# P12_SPI_NAND_FLASH.net
KiCad netlist of a schematic drawn in Altium Designer
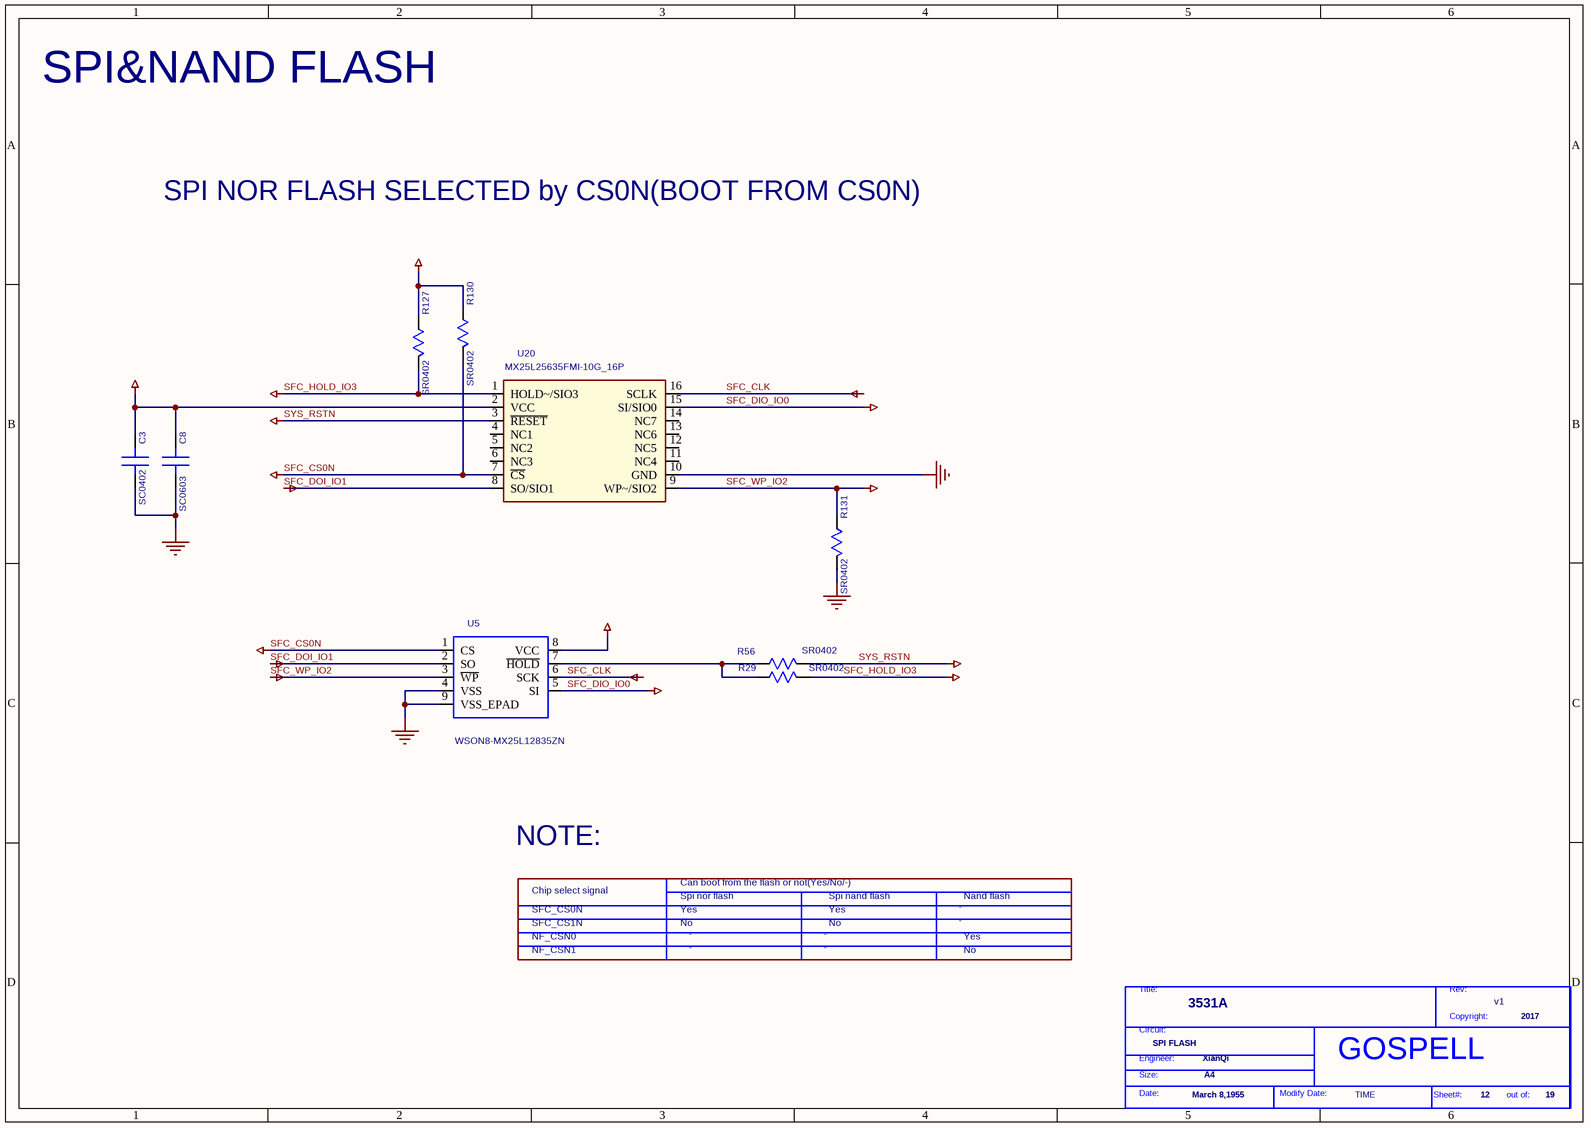
[diagram p0: P12 SPI&NAND FLASH.SchDoc]

(export (version "E")
  (design (tool "Eeschema 10.0.6"))
  (components
    (comp (ref "C3") (value "SC0402") (libsource (lib "*") (part "C_0_Dup2")))
    (comp (ref "C8") (value "SC0603") (libsource (lib "*") (part "C_0_Dup1")))
    (comp (ref "R29") (value "SR0402") (libsource (lib "*") (part "R_1")))
    (comp (ref "R56") (value "SR0402") (libsource (lib "*") (part "R_1")))
    (comp (ref "R127") (value "SR0402") (libsource (lib "*") (part "R_1")))
    (comp (ref "R130") (value "SR0402") (libsource (lib "*") (part "R_1")))
    (comp (ref "R131") (value "SR0402") (libsource (lib "*") (part "R_1")))
    (comp (ref "U5") (value "WSON8-MX25L12835ZN") (libsource (lib "*") (part "SPI_NAND_FLASH_0")))
    (comp (ref "U20")
      (value "SOP16-50-300A")
      (fields (field (name "DEVICE") "MX25L25635FMI-10G_16P"))
      (libsource (lib "*") (part "MX25L25635EMI-12G_1"))
    )
  )
  (nets
    (net (code "1") (name "3V3") (class "Default")
      (node (ref "C3") (pin "1") (pinfunction "A_1") (pintype "passive"))
      (node (ref "C8") (pin "1") (pinfunction "A_1") (pintype "passive"))
      (node (ref "R127") (pin "1") (pinfunction "A_1") (pintype "passive"))
      (node (ref "R130") (pin "1") (pinfunction "A_1") (pintype "passive"))
      (node (ref "U20") (pin "2") (pinfunction "VCC_2") (pintype "passive"))
      (node (ref "U5") (pin "8") (pinfunction "VCC_8") (pintype "passive"))
    )
    (net (code "2") (name "GND") (class "Default")
      (node (ref "C3") (pin "2") (pinfunction "B_2") (pintype "passive"))
      (node (ref "C8") (pin "2") (pinfunction "B_2") (pintype "passive"))
      (node (ref "R131") (pin "2") (pinfunction "B_2") (pintype "passive"))
      (node (ref "U20") (pin "10") (pinfunction "GND_10") (pintype "passive"))
      (node (ref "U5") (pin "4") (pinfunction "VSS_4") (pintype "passive"))
      (node (ref "U5") (pin "9") (pinfunction "VSS_EPAD_9") (pintype "passive"))
    )
    (net (code "3") (name "Net-(R29-A)") (class "Default")
      (node (ref "R29") (pin "1") (pinfunction "A_1") (pintype "passive"))
      (node (ref "R56") (pin "1") (pinfunction "A_1") (pintype "passive"))
      (node (ref "U5") (pin "7") (pinfunction "~{HOLD}_7") (pintype "passive"))
    )
    (net (code "4") (name "SFC_CLK") (class "Default")
      (node (ref "U20") (pin "16") (pinfunction "SCLK_16") (pintype "passive"))
      (node (ref "U5") (pin "6") (pinfunction "SCK_6") (pintype "passive"))
    )
    (net (code "5") (name "SFC_CS0N") (class "Default")
      (node (ref "R130") (pin "2") (pinfunction "B_2") (pintype "passive"))
      (node (ref "U20") (pin "7") (pinfunction "~{CS}_7") (pintype "passive"))
      (node (ref "U5") (pin "1") (pinfunction "CS_1") (pintype "passive"))
    )
    (net (code "6") (name "SFC_DIO_IO0") (class "Default")
      (node (ref "U20") (pin "15") (pinfunction "SI/SIO0_15") (pintype "passive"))
      (node (ref "U5") (pin "5") (pinfunction "SI_5") (pintype "passive"))
    )
    (net (code "7") (name "SFC_DOI_IO1") (class "Default")
      (node (ref "U20") (pin "8") (pinfunction "SO/SIO1_8") (pintype "passive"))
      (node (ref "U5") (pin "2") (pinfunction "SO_2") (pintype "passive"))
    )
    (net (code "8") (name "SFC_HOLD_IO3") (class "Default")
      (node (ref "R127") (pin "2") (pinfunction "B_2") (pintype "passive"))
      (node (ref "R29") (pin "2") (pinfunction "B_2") (pintype "passive"))
      (node (ref "U20") (pin "1") (pinfunction "HOLD~/SIO3_1") (pintype "passive"))
    )
    (net (code "9") (name "SFC_WP_IO2") (class "Default")
      (node (ref "R131") (pin "1") (pinfunction "A_1") (pintype "passive"))
      (node (ref "U20") (pin "9") (pinfunction "WP~/SIO2_9") (pintype "passive"))
      (node (ref "U5") (pin "3") (pinfunction "~{WP}_3") (pintype "passive"))
    )
    (net (code "10") (name "SYS_RSTN") (class "Default")
      (node (ref "R56") (pin "2") (pinfunction "B_2") (pintype "passive"))
      (node (ref "U20") (pin "3") (pinfunction "~{RESET}_3") (pintype "passive"))
    )
    (net (code "11") (name "unconnected-(U20-NC1-Pad4)") (class "Default")
      (node (ref "U20") (pin "4") (pinfunction "NC1_4") (pintype "passive"))
    )
    (net (code "12") (name "unconnected-(U20-NC2-Pad5)") (class "Default")
      (node (ref "U20") (pin "5") (pinfunction "NC2_5") (pintype "passive"))
    )
    (net (code "13") (name "unconnected-(U20-NC3-Pad6)") (class "Default")
      (node (ref "U20") (pin "6") (pinfunction "NC3_6") (pintype "passive"))
    )
    (net (code "14") (name "unconnected-(U20-NC4-Pad11)") (class "Default")
      (node (ref "U20") (pin "11") (pinfunction "NC4_11") (pintype "passive"))
    )
    (net (code "15") (name "unconnected-(U20-NC5-Pad12)") (class "Default")
      (node (ref "U20") (pin "12") (pinfunction "NC5_12") (pintype "passive"))
    )
    (net (code "16") (name "unconnected-(U20-NC6-Pad13)") (class "Default")
      (node (ref "U20") (pin "13") (pinfunction "NC6_13") (pintype "passive"))
    )
    (net (code "17") (name "unconnected-(U20-NC7-Pad14)") (class "Default")
      (node (ref "U20") (pin "14") (pinfunction "NC7_14") (pintype "passive"))
    )
  )
)
